# Complete.net
KiCad netlist of a schematic drawn in Altium Designer
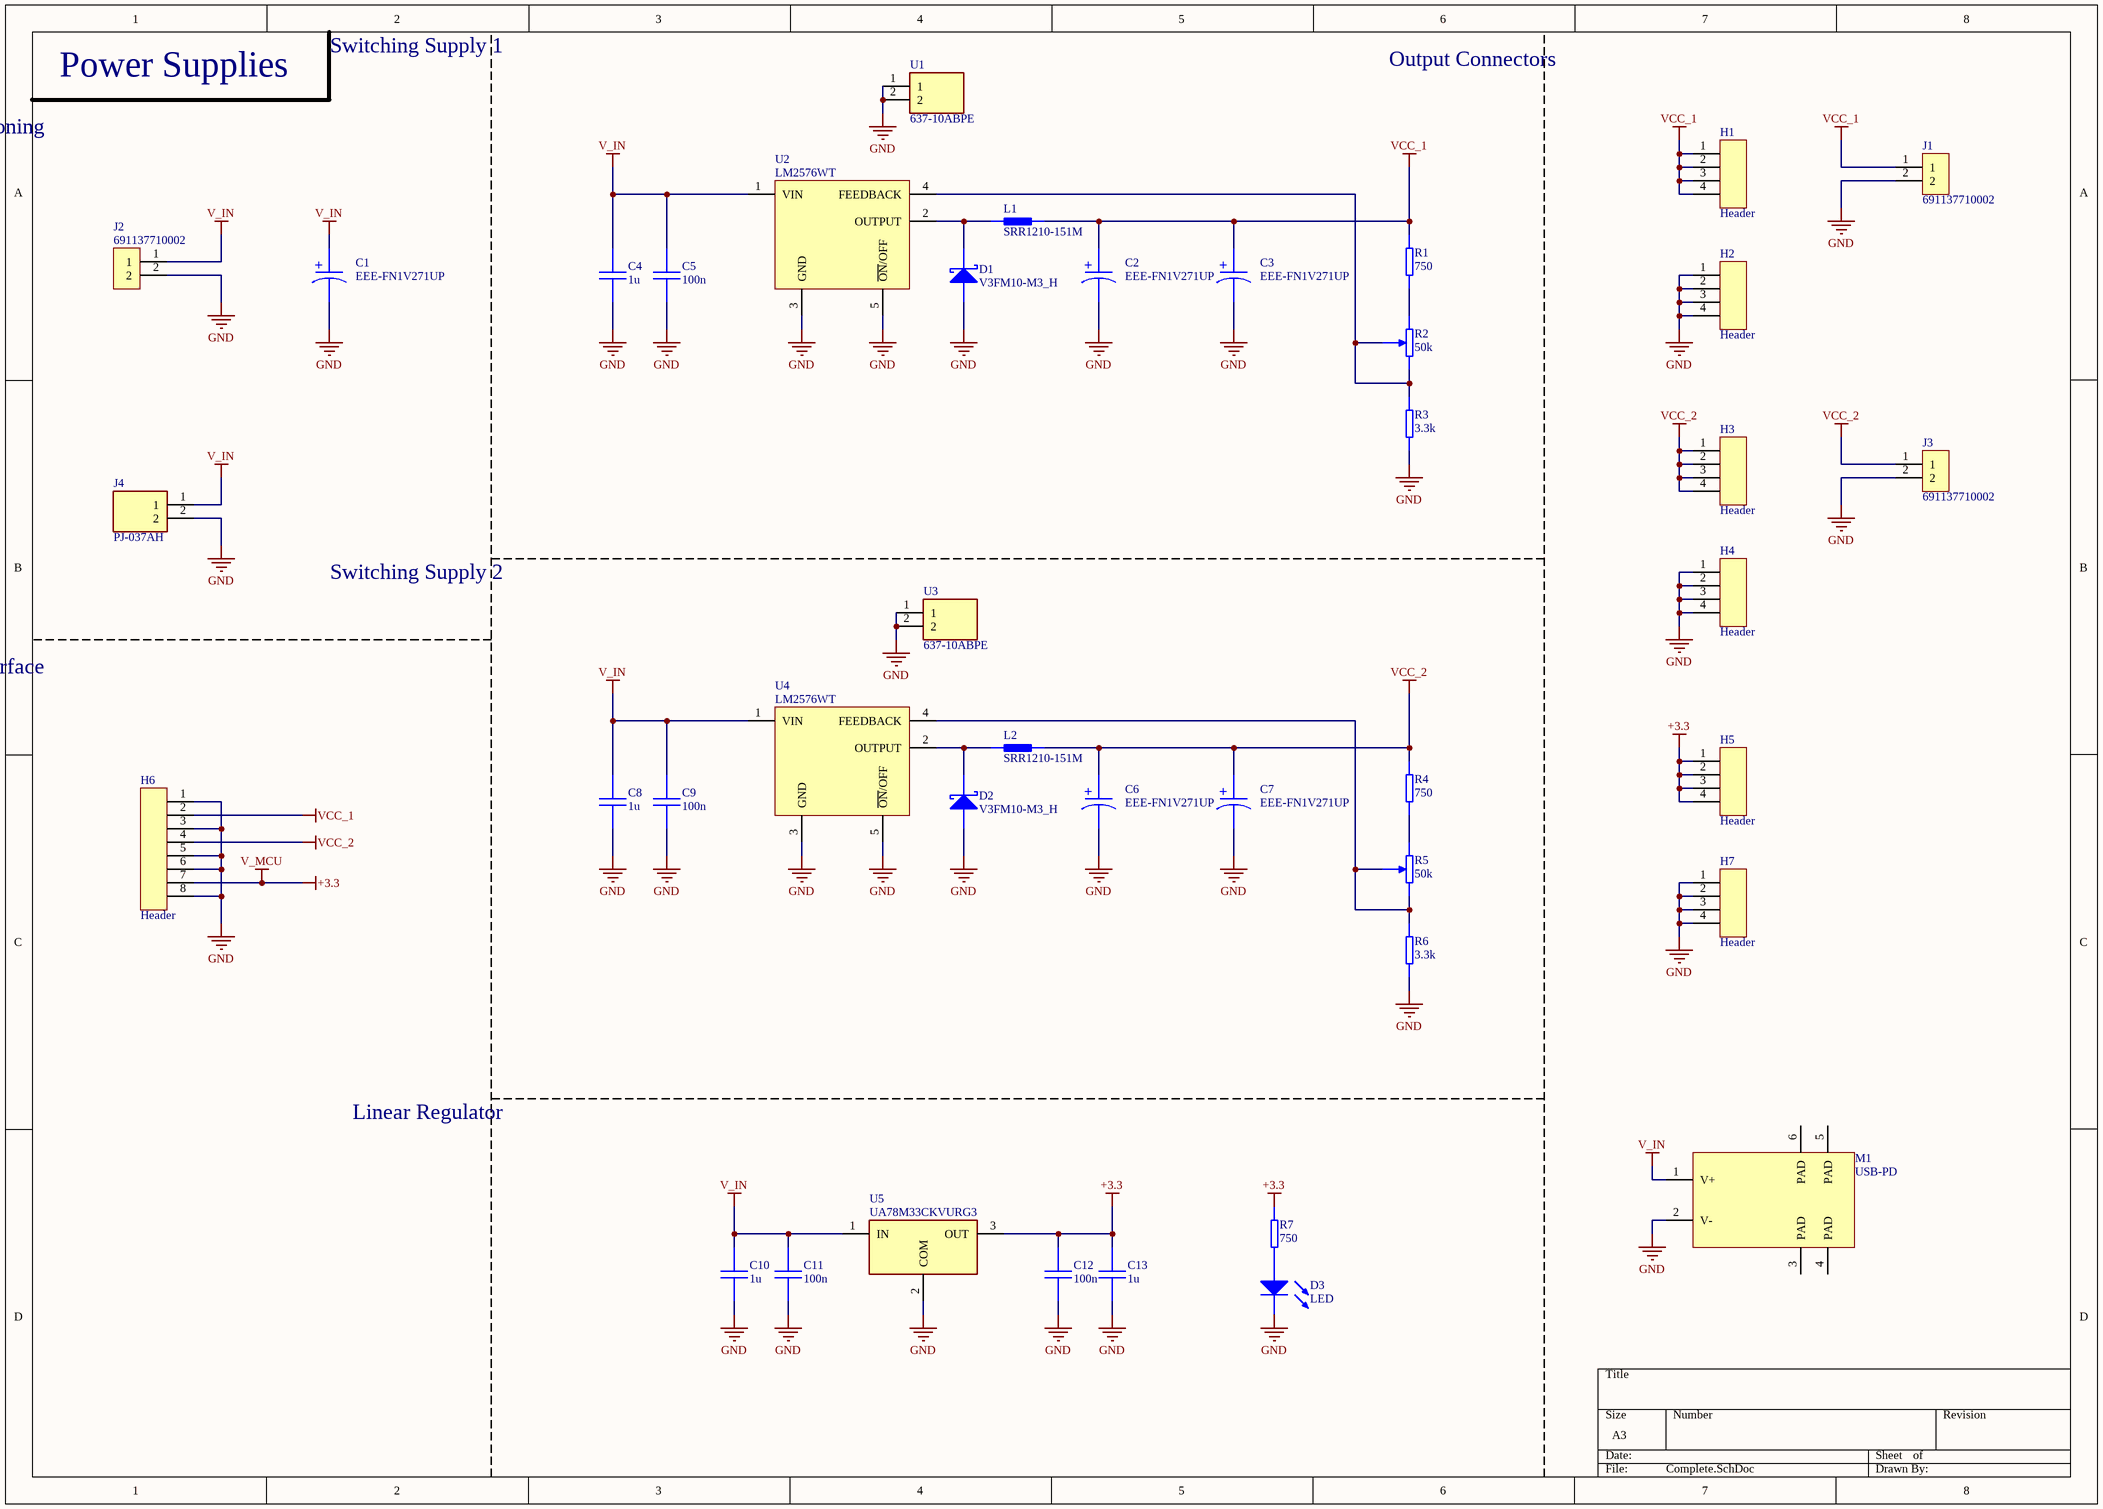
[diagram p0: Complete.SchDoc]

(export (version "E")
  (design (tool "Eeschema 10.0.6"))
  (components
    (comp (ref "C1")
      (value "EEE-FN1V271UP")
      (footprint "EEHZT1E331UP")
      (description "Capacitor Polarised")
      (fields (field (name "MOUSER PART NUMBER") "667-EEE-FN1V271UP"))
      (libsource (lib "TD") (part "EEE-FN1V271UP"))
    )
    (comp (ref "C2")
      (value "EEE-FN1V271UP")
      (footprint "EEHZT1E331UP")
      (description "Capacitor Polarised")
      (fields (field (name "MOUSER PART NUMBER") "667-EEE-FN1V271UP"))
      (libsource (lib "TD") (part "EEE-FN1V271UP"))
    )
    (comp (ref "C3")
      (value "EEE-FN1V271UP")
      (footprint "EEHZT1E331UP")
      (description "Capacitor Polarised")
      (fields (field (name "MOUSER PART NUMBER") "667-EEE-FN1V271UP"))
      (libsource (lib "TD") (part "EEE-FN1V271UP"))
    )
    (comp (ref "C4")
      (value "1u")
      (footprint "CAP0805")
      (description "Non Polarized Capacitor")
      (libsource (lib "TD") (part "Capacitor - Non Polarized"))
    )
    (comp (ref "C5")
      (value "100n")
      (footprint "CAP0805")
      (description "Non Polarized Capacitor")
      (libsource (lib "TD") (part "Capacitor - Non Polarized"))
    )
    (comp (ref "C6")
      (value "EEE-FN1V271UP")
      (footprint "EEHZT1E331UP")
      (description "Capacitor Polarised")
      (fields (field (name "MOUSER PART NUMBER") "667-EEE-FN1V271UP"))
      (libsource (lib "TD") (part "EEE-FN1V271UP"))
    )
    (comp (ref "C7")
      (value "EEE-FN1V271UP")
      (footprint "EEHZT1E331UP")
      (description "Capacitor Polarised")
      (fields (field (name "MOUSER PART NUMBER") "667-EEE-FN1V271UP"))
      (libsource (lib "TD") (part "EEE-FN1V271UP"))
    )
    (comp (ref "C8")
      (value "1u")
      (footprint "CAP0805")
      (description "Non Polarized Capacitor")
      (libsource (lib "TD") (part "Capacitor - Non Polarized"))
    )
    (comp (ref "C9")
      (value "100n")
      (footprint "CAP0805")
      (description "Non Polarized Capacitor")
      (libsource (lib "TD") (part "Capacitor - Non Polarized"))
    )
    (comp (ref "C10")
      (value "1u")
      (footprint "CAP0805")
      (description "Non Polarized Capacitor")
      (libsource (lib "TD") (part "Capacitor - Non Polarized"))
    )
    (comp (ref "C11")
      (value "100n")
      (footprint "CAP0805")
      (description "Non Polarized Capacitor")
      (libsource (lib "TD") (part "Capacitor - Non Polarized"))
    )
    (comp (ref "C12")
      (value "100n")
      (footprint "CAP0805")
      (description "Non Polarized Capacitor")
      (libsource (lib "TD") (part "Capacitor - Non Polarized"))
    )
    (comp (ref "C13")
      (value "1u")
      (footprint "CAP0805")
      (description "Non Polarized Capacitor")
      (libsource (lib "TD") (part "Capacitor - Non Polarized"))
    )
    (comp (ref "D1")
      (value "V3FM10-M3_H")
      (footprint "DO-219AB")
      (description "Schottky Diode")
      (fields
        (field (name "MANUFACTURER_PART_NUMBER") "V3FM10-M3/H")
        (field (name "MOUSER PART NUMBER") "78-V3FM10-M3/H")
      )
      (libsource (lib "TD") (part "V3FM10-M3_H"))
    )
    (comp (ref "D2")
      (value "V3FM10-M3_H")
      (footprint "DO-219AB")
      (description "Schottky Diode")
      (fields
        (field (name "MANUFACTURER_PART_NUMBER") "V3FM10-M3/H")
        (field (name "MOUSER PART NUMBER") "78-V3FM10-M3/H")
      )
      (libsource (lib "TD") (part "V3FM10-M3_H"))
    )
    (comp (ref "D3")
      (value "LED")
      (footprint "LEDM2012X80N")
      (description "General Purpose LED")
      (libsource (lib "TD") (part "LED"))
    )
    (comp (ref "H1")
      (value "Header")
      (footprint "Header_1X4")
      (description "4-Pin Header")
      (libsource (lib "TD") (part "4-Pin Header"))
    )
    (comp (ref "H2")
      (value "Header")
      (footprint "Header_1X4")
      (description "4-Pin Header")
      (libsource (lib "TD") (part "4-Pin Header"))
    )
    (comp (ref "H3")
      (value "Header")
      (footprint "Header_1X4")
      (description "4-Pin Header")
      (libsource (lib "TD") (part "4-Pin Header"))
    )
    (comp (ref "H4")
      (value "Header")
      (footprint "Header_1X4")
      (description "4-Pin Header")
      (libsource (lib "TD") (part "4-Pin Header"))
    )
    (comp (ref "H5")
      (value "Header")
      (footprint "Header_1X4")
      (description "4-Pin Header")
      (libsource (lib "TD") (part "4-Pin Header"))
    )
    (comp (ref "H6")
      (value "Header")
      (footprint "Header_1X8")
      (description "8-Pin Header")
      (libsource (lib "TD") (part "8-Pin Header"))
    )
    (comp (ref "H7")
      (value "Header")
      (footprint "Header_1X4")
      (description "4-Pin Header")
      (libsource (lib "TD") (part "4-Pin Header"))
    )
    (comp (ref "J1")
      (value "691137710002")
      (footprint "SHDR2W70P0X500_1X2_1000X750X1160P")
      (description "Connector")
      (fields (field (name "MOUSER PART NUMBER") "710-691137710002"))
      (libsource (lib "") (part "691137710002_1"))
    )
    (comp (ref "J2")
      (value "691137710002")
      (footprint "SHDR2W70P0X500_1X2_1000X750X1160P")
      (description "Connector")
      (fields (field (name "MOUSER PART NUMBER") "710-691137710002"))
      (libsource (lib "TD") (part "691137710002"))
    )
    (comp (ref "J3")
      (value "691137710002")
      (footprint "SHDR2W70P0X500_1X2_1000X750X1160P")
      (description "Connector")
      (fields (field (name "MOUSER PART NUMBER") "710-691137710002"))
      (libsource (lib "") (part "691137710002_1"))
    )
    (comp (ref "J4")
      (value "PJ-037AH")
      (footprint "PJ037AH")
      (description "Connector")
      (fields (field (name "MOUSER PART NUMBER") "490-PJ-037AH"))
      (libsource (lib "TD") (part "PJ-037AH"))
    )
    (comp (ref "L1")
      (value "SRR1210-151M")
      (footprint "INDPM120120X1000N-D")
      (description "Inductor")
      (fields (field (name "MOUSER PART NUMBER") "652-SRR1210-151M"))
      (libsource (lib "TD") (part "SRR1210-151M"))
    )
    (comp (ref "L2")
      (value "SRR1210-151M")
      (footprint "INDPM120120X1000N-D")
      (description "Inductor")
      (fields (field (name "MOUSER PART NUMBER") "652-SRR1210-151M"))
      (libsource (lib "TD") (part "SRR1210-151M"))
    )
    (comp (ref "M1")
      (value "USB-PD")
      (footprint "USB_C-PD")
      (libsource (lib "IEEE_Workshop_SCH") (part "USB-PD"))
    )
    (comp (ref "R1")
      (value "750")
      (footprint "RESC0805")
      (description "Resistor")
      (libsource (lib "TD") (part "Resistor"))
    )
    (comp (ref "R2")
      (value "50k")
      (footprint "3339P1103LF")
      (description "Potentionmeter")
      (libsource (lib "TD") (part "Potentiometer"))
    )
    (comp (ref "R3")
      (value "3.3k")
      (footprint "RESC0805")
      (description "Resistor")
      (libsource (lib "TD") (part "Resistor"))
    )
    (comp (ref "R4")
      (value "750")
      (footprint "RESC0805")
      (description "Resistor")
      (libsource (lib "TD") (part "Resistor"))
    )
    (comp (ref "R5")
      (value "50k")
      (footprint "3339P1103LF")
      (description "Potentionmeter")
      (libsource (lib "TD") (part "Potentiometer"))
    )
    (comp (ref "R6")
      (value "3.3k")
      (footprint "RESC0805")
      (description "Resistor")
      (libsource (lib "TD") (part "Resistor"))
    )
    (comp (ref "R7")
      (value "750")
      (footprint "RESC0805")
      (description "Resistor")
      (libsource (lib "TD") (part "Resistor"))
    )
    (comp (ref "U1")
      (value "637-10ABPE")
      (footprint "63710ABPE")
      (description "Undefined or Miscellaneous")
      (fields (field (name "MOUSER PART NUMBER") "567-637-10ABPE"))
      (libsource (lib "*") (part "637-10ABPE"))
    )
    (comp (ref "U2")
      (value "LM2576WT")
      (footprint "TO-220-5")
      (description "Integrated Circuit")
      (fields
        (field (name "MANUFACTURER_PART_NUMBER") "LM2576WU-TR")
        (field (name "MOUSER PART NUMBER") "998-LM2576WT")
      )
      (libsource (lib "TD") (part "LM2576WT"))
    )
    (comp (ref "U3")
      (value "637-10ABPE")
      (footprint "63710ABPE")
      (description "Undefined or Miscellaneous")
      (fields (field (name "MOUSER PART NUMBER") "567-637-10ABPE"))
      (libsource (lib "*") (part "637-10ABPE"))
    )
    (comp (ref "U4")
      (value "LM2576WT")
      (footprint "TO-220-5")
      (description "Integrated Circuit")
      (fields
        (field (name "MANUFACTURER_PART_NUMBER") "LM2576WU-TR")
        (field (name "MOUSER PART NUMBER") "998-LM2576WT")
      )
      (libsource (lib "TD") (part "LM2576WT"))
    )
    (comp (ref "U5")
      (value "UA78M33CKVURG3")
      (footprint "TO-252-3")
      (description "Linear Voltage Regulator")
      (fields (field (name "MOUSER PART NUMBER") "595-UA78M33CKVURG3"))
      (libsource (lib "TD") (part "UA78M33CKVURG3"))
    )
  )
  (nets
    (net (code "1") (name "+3.3") (class "Default")
      (node (ref "C12") (pin "1") (pintype "passive"))
      (node (ref "C13") (pin "1") (pintype "passive"))
      (node (ref "H5") (pin "1") (pintype "passive"))
      (node (ref "H5") (pin "2") (pintype "passive"))
      (node (ref "H5") (pin "3") (pintype "passive"))
      (node (ref "H5") (pin "4") (pintype "passive"))
      (node (ref "H6") (pin "7") (pintype "passive"))
      (node (ref "R7") (pin "1") (pintype "passive"))
      (node (ref "U5") (pin "3") (pinfunction "OUT_3") (pintype "passive"))
    )
    (net (code "2") (name "GND") (class "Default")
      (node (ref "C1") (pin "2") (pintype "passive"))
      (node (ref "C10") (pin "2") (pintype "passive"))
      (node (ref "C11") (pin "2") (pintype "passive"))
      (node (ref "C12") (pin "2") (pintype "passive"))
      (node (ref "C13") (pin "2") (pintype "passive"))
      (node (ref "C2") (pin "2") (pintype "passive"))
      (node (ref "C3") (pin "2") (pintype "passive"))
      (node (ref "C4") (pin "2") (pintype "passive"))
      (node (ref "C5") (pin "2") (pintype "passive"))
      (node (ref "C6") (pin "2") (pintype "passive"))
      (node (ref "C7") (pin "2") (pintype "passive"))
      (node (ref "C8") (pin "2") (pintype "passive"))
      (node (ref "C9") (pin "2") (pintype "passive"))
      (node (ref "D1") (pin "2") (pinfunction "A_2") (pintype "passive"))
      (node (ref "D2") (pin "2") (pinfunction "A_2") (pintype "passive"))
      (node (ref "D3") (pin "1") (pinfunction "K_1") (pintype "passive"))
      (node (ref "H2") (pin "1") (pintype "passive"))
      (node (ref "H2") (pin "2") (pintype "passive"))
      (node (ref "H2") (pin "3") (pintype "passive"))
      (node (ref "H2") (pin "4") (pintype "passive"))
      (node (ref "H4") (pin "1") (pintype "passive"))
      (node (ref "H4") (pin "2") (pintype "passive"))
      (node (ref "H4") (pin "3") (pintype "passive"))
      (node (ref "H4") (pin "4") (pintype "passive"))
      (node (ref "H6") (pin "1") (pintype "passive"))
      (node (ref "H6") (pin "3") (pintype "passive"))
      (node (ref "H6") (pin "5") (pintype "passive"))
      (node (ref "H6") (pin "6") (pintype "passive"))
      (node (ref "H6") (pin "8") (pintype "passive"))
      (node (ref "H7") (pin "1") (pintype "passive"))
      (node (ref "H7") (pin "2") (pintype "passive"))
      (node (ref "H7") (pin "3") (pintype "passive"))
      (node (ref "H7") (pin "4") (pintype "passive"))
      (node (ref "J1") (pin "2") (pinfunction "2_2") (pintype "passive"))
      (node (ref "J2") (pin "2") (pinfunction "2_2") (pintype "passive"))
      (node (ref "J3") (pin "2") (pinfunction "2_2") (pintype "passive"))
      (node (ref "J4") (pin "2") (pinfunction "2_2") (pintype "passive"))
      (node (ref "M1") (pin "2") (pinfunction "V-_2") (pintype "passive"))
      (node (ref "R3") (pin "2") (pintype "passive"))
      (node (ref "R6") (pin "2") (pintype "passive"))
      (node (ref "U1") (pin "1") (pinfunction "1_1") (pintype "passive"))
      (node (ref "U1") (pin "2") (pinfunction "2_2") (pintype "passive"))
      (node (ref "U2") (pin "3") (pinfunction "GND_3") (pintype "passive"))
      (node (ref "U2") (pin "5") (pinfunction "~{ON}/OFF_5") (pintype "passive"))
      (node (ref "U3") (pin "1") (pinfunction "1_1") (pintype "passive"))
      (node (ref "U3") (pin "2") (pinfunction "2_2") (pintype "passive"))
      (node (ref "U4") (pin "3") (pinfunction "GND_3") (pintype "passive"))
      (node (ref "U4") (pin "5") (pinfunction "~{ON}/OFF_5") (pintype "passive"))
      (node (ref "U5") (pin "2") (pinfunction "COM_2") (pintype "passive"))
    )
    (net (code "3") (name "Net-(D1-K)") (class "Default")
      (node (ref "D1") (pin "1") (pinfunction "K_1") (pintype "passive"))
      (node (ref "L1") (pin "1") (pintype "passive"))
      (node (ref "U2") (pin "2") (pinfunction "OUTPUT_2") (pintype "passive"))
    )
    (net (code "4") (name "Net-(D2-K)") (class "Default")
      (node (ref "D2") (pin "1") (pinfunction "K_1") (pintype "passive"))
      (node (ref "L2") (pin "1") (pintype "passive"))
      (node (ref "U4") (pin "2") (pinfunction "OUTPUT_2") (pintype "passive"))
    )
    (net (code "5") (name "Net-(D3-A)") (class "Default")
      (node (ref "D3") (pin "2") (pinfunction "A_2") (pintype "passive"))
      (node (ref "R7") (pin "2") (pintype "passive"))
    )
    (net (code "6") (name "Net-(R1-Pad2)") (class "Default")
      (node (ref "R1") (pin "2") (pintype "passive"))
      (node (ref "R2") (pin "1") (pintype "passive"))
    )
    (net (code "7") (name "Net-(R4-Pad2)") (class "Default")
      (node (ref "R4") (pin "2") (pintype "passive"))
      (node (ref "R5") (pin "1") (pintype "passive"))
    )
    (net (code "8") (name "Net-(U2-FEEDBACK)") (class "Default")
      (node (ref "R2") (pin "2") (pintype "passive"))
      (node (ref "R2") (pin "3") (pintype "passive"))
      (node (ref "R3") (pin "1") (pintype "passive"))
      (node (ref "U2") (pin "4") (pinfunction "FEEDBACK_4") (pintype "passive"))
    )
    (net (code "9") (name "Net-(U4-FEEDBACK)") (class "Default")
      (node (ref "R5") (pin "2") (pintype "passive"))
      (node (ref "R5") (pin "3") (pintype "passive"))
      (node (ref "R6") (pin "1") (pintype "passive"))
      (node (ref "U4") (pin "4") (pinfunction "FEEDBACK_4") (pintype "passive"))
    )
    (net (code "10") (name "VCC_1") (class "Default")
      (node (ref "C2") (pin "1") (pintype "passive"))
      (node (ref "C3") (pin "1") (pintype "passive"))
      (node (ref "H1") (pin "1") (pintype "passive"))
      (node (ref "H1") (pin "2") (pintype "passive"))
      (node (ref "H1") (pin "3") (pintype "passive"))
      (node (ref "H1") (pin "4") (pintype "passive"))
      (node (ref "H6") (pin "2") (pintype "passive"))
      (node (ref "J1") (pin "1") (pinfunction "1_1") (pintype "passive"))
      (node (ref "L1") (pin "2") (pintype "passive"))
      (node (ref "R1") (pin "1") (pintype "passive"))
    )
    (net (code "11") (name "VCC_2") (class "Default")
      (node (ref "C6") (pin "1") (pintype "passive"))
      (node (ref "C7") (pin "1") (pintype "passive"))
      (node (ref "H3") (pin "1") (pintype "passive"))
      (node (ref "H3") (pin "2") (pintype "passive"))
      (node (ref "H3") (pin "3") (pintype "passive"))
      (node (ref "H3") (pin "4") (pintype "passive"))
      (node (ref "H6") (pin "4") (pintype "passive"))
      (node (ref "J3") (pin "1") (pinfunction "1_1") (pintype "passive"))
      (node (ref "L2") (pin "2") (pintype "passive"))
      (node (ref "R4") (pin "1") (pintype "passive"))
    )
    (net (code "12") (name "V_IN") (class "Default")
      (node (ref "C1") (pin "1") (pintype "passive"))
      (node (ref "C10") (pin "1") (pintype "passive"))
      (node (ref "C11") (pin "1") (pintype "passive"))
      (node (ref "C4") (pin "1") (pintype "passive"))
      (node (ref "C5") (pin "1") (pintype "passive"))
      (node (ref "C8") (pin "1") (pintype "passive"))
      (node (ref "C9") (pin "1") (pintype "passive"))
      (node (ref "J2") (pin "1") (pinfunction "1_1") (pintype "passive"))
      (node (ref "J4") (pin "1") (pinfunction "1_1") (pintype "passive"))
      (node (ref "M1") (pin "1") (pinfunction "V+_1") (pintype "passive"))
      (node (ref "U2") (pin "1") (pinfunction "VIN_1") (pintype "passive"))
      (node (ref "U4") (pin "1") (pinfunction "VIN_1") (pintype "passive"))
      (node (ref "U5") (pin "1") (pinfunction "IN_1") (pintype "passive"))
    )
    (net (code "13") (name "unconnected-(M1-PAD-Pad3)") (class "Default")
      (node (ref "M1") (pin "3") (pinfunction "PAD_3") (pintype "passive"))
    )
    (net (code "14") (name "unconnected-(M1-PAD-Pad4)") (class "Default")
      (node (ref "M1") (pin "4") (pinfunction "PAD_4") (pintype "passive"))
    )
    (net (code "15") (name "unconnected-(M1-PAD-Pad5)") (class "Default")
      (node (ref "M1") (pin "5") (pinfunction "PAD_5") (pintype "passive"))
    )
    (net (code "16") (name "unconnected-(M1-PAD-Pad6)") (class "Default")
      (node (ref "M1") (pin "6") (pinfunction "PAD_6") (pintype "passive"))
    )
  )
)
